# 20190105_ORIGAMI_V1-V.net
KiCad netlist of a schematic drawn in EAGLE
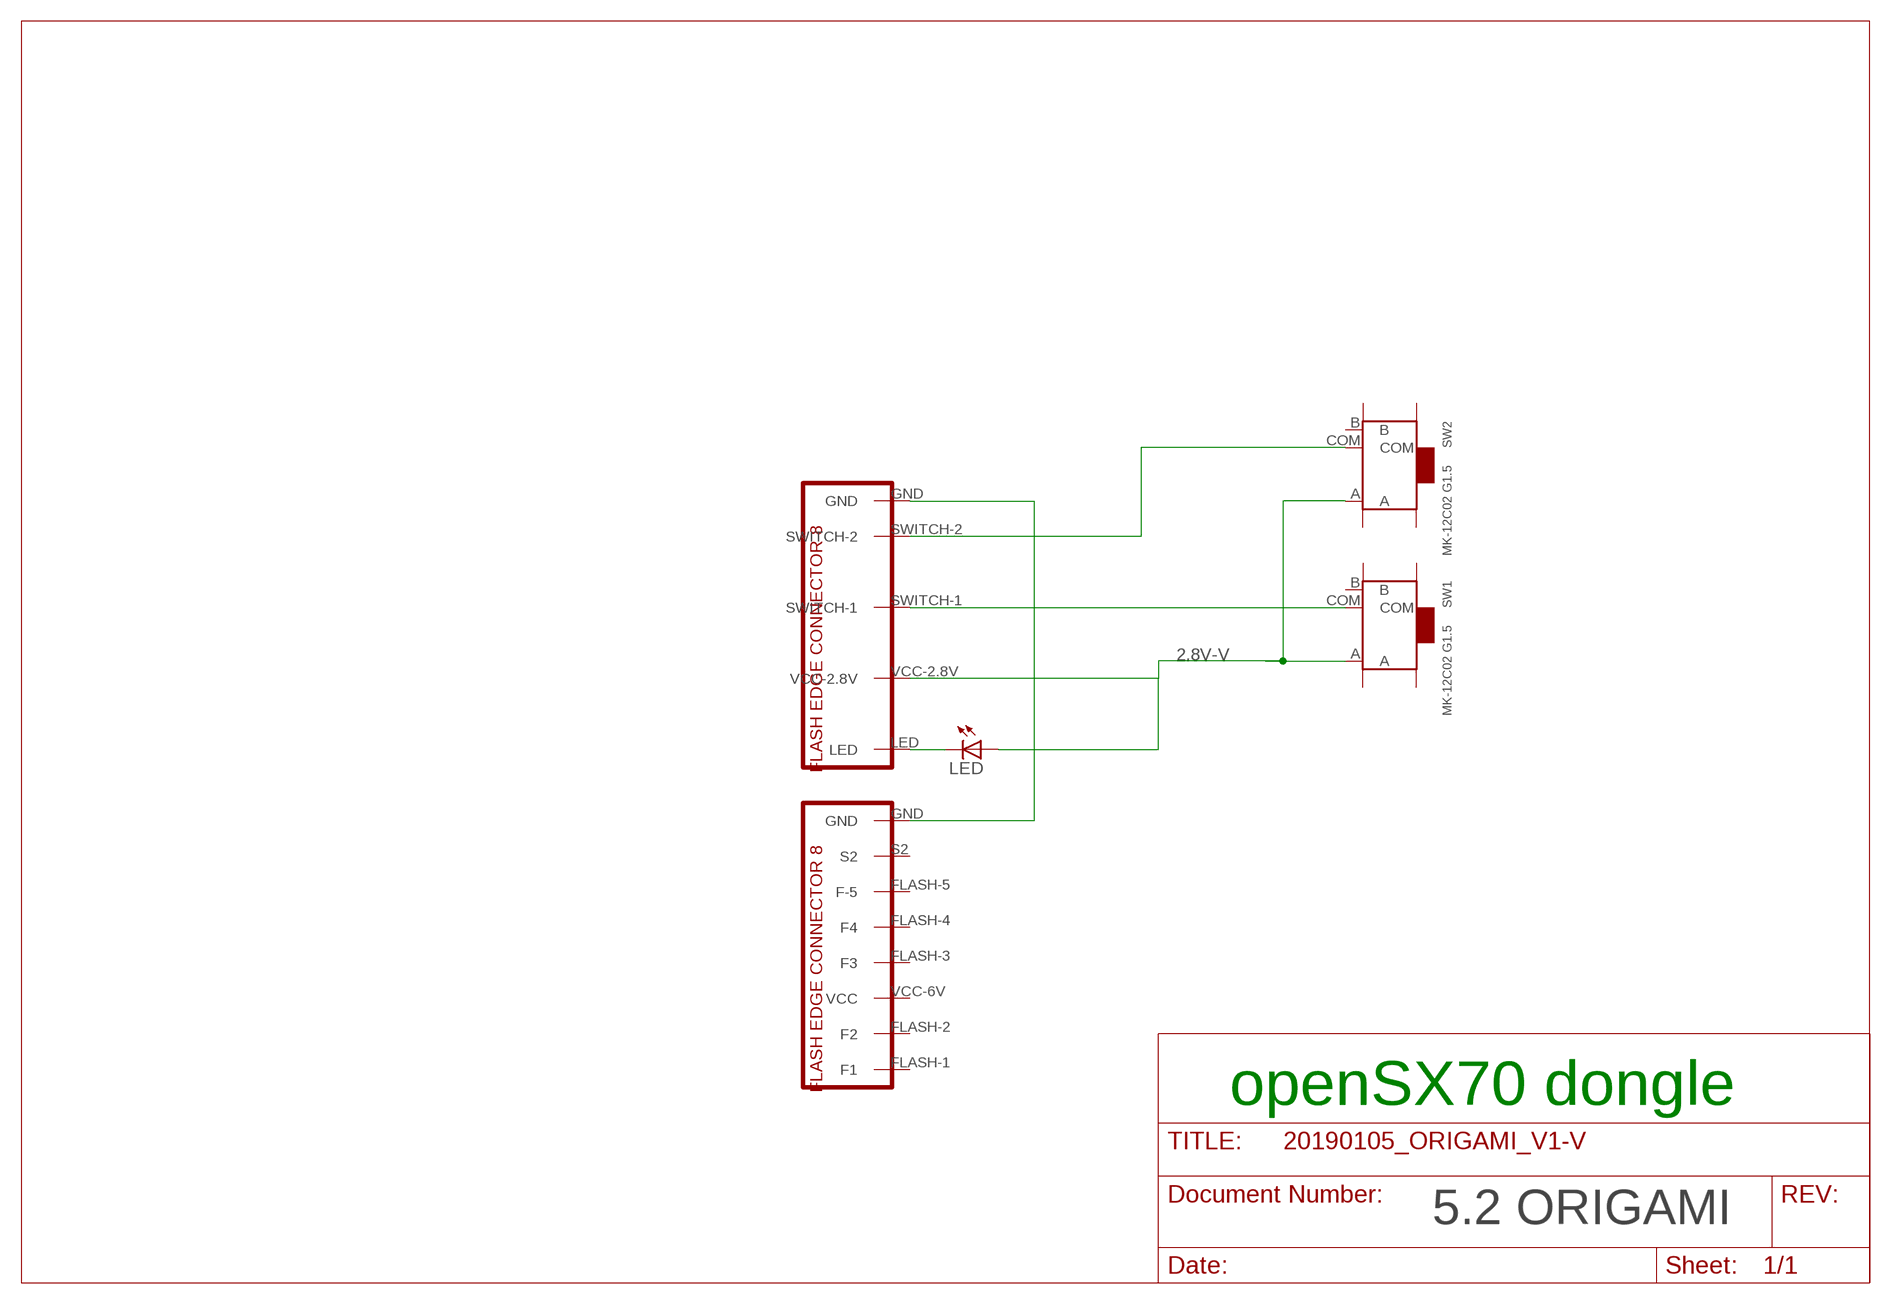
[diagram p0: schematic, sheet 1]

(export (version "E")
  (design (tool "Eeschema 10.0.6"))
  (components
    (comp (ref "LED")
      (value "LEDCHIP-LED0805")
      (footprint "eagle-import:CHIP-LED0805")
      (libsource (lib "eagle-import") (part "LEDCHIP-LED0805"))
    )
    (comp (ref "SW1")
      (value "MK-12C02 G1.5")
      (footprint "eagle-import:SW7-SMD-L6.7X2.7X3.2MM")
      (libsource (lib "eagle-import") (part "SMD-TOGGLE-SWITCH-ON-ON(3+4P-6.7X2.7MM)"))
    )
    (comp (ref "SW2")
      (value "MK-12C02 G1.5")
      (footprint "eagle-import:SW7-SMD-L6.7X2.7X3.2MM")
      (libsource (lib "eagle-import") (part "SMD-TOGGLE-SWITCH-ON-ON(3+4P-6.7X2.7MM)"))
    )
    (comp (ref "U$1")
      (value "FLASH-BRIDGE-SW1-SW2-LED-SMALL")
      (footprint "eagle-import:FLASH-8-BRIDGE-SW1-SW2-LED-SMALL")
      (libsource (lib "eagle-import") (part "FLASH-BRIDGE-SW1-SW2-LED-SMALL"))
    )
    (comp (ref "U$2")
      (value "SX70-FLASH-EDGE8-MALE-LONG")
      (footprint "eagle-import:SX70-FLASH-EDGE8-2")
      (libsource (lib "eagle-import") (part "SX70-FLASH-EDGE8-MALE-LONG"))
    )
  )
  (nets
    (net (code "1") (name "/2.8V-V") (class "Default")
      (node (ref "LED") (pin "A") (pinfunction "A_A") (pintype "passive"))
      (node (ref "SW1") (pin "A") (pinfunction "A_A") (pintype "bidirectional"))
      (node (ref "SW2") (pin "A") (pinfunction "A_A") (pintype "bidirectional"))
      (node (ref "U$1") (pin "VCC-2.8V") (pinfunction "VCC-2.8V_VCC-2.8V") (pintype "bidirectional"))
    )
    (net (code "2") (name "Net-(LED-PadC)") (class "Default")
      (node (ref "LED") (pin "C") (pinfunction "C_C") (pintype "passive"))
      (node (ref "U$1") (pin "LED") (pinfunction "LED_LED") (pintype "bidirectional"))
    )
    (net (code "3") (name "Net-(SW1-PadCOM)") (class "Default")
      (node (ref "SW1") (pin "COM") (pinfunction "COM_COM") (pintype "bidirectional"))
      (node (ref "U$1") (pin "SWITCH-1") (pinfunction "SWITCH-1_SWITCH-1") (pintype "bidirectional"))
    )
    (net (code "4") (name "Net-(SW2-PadCOM)") (class "Default")
      (node (ref "SW2") (pin "COM") (pinfunction "COM_COM") (pintype "bidirectional"))
      (node (ref "U$1") (pin "SWITCH-2") (pinfunction "SWITCH-2_SWITCH-2") (pintype "bidirectional"))
    )
    (net (code "5") (name "Net-(U$1-PadGND)") (class "Default")
      (node (ref "U$1") (pin "GND") (pinfunction "GND_GND") (pintype "bidirectional"))
      (node (ref "U$2") (pin "GND") (pinfunction "GND_GND") (pintype "bidirectional"))
    )
    (net (code "6") (name "unconnected-(SW1-PadB)") (class "Default")
      (node (ref "SW1") (pin "B") (pinfunction "B_B") (pintype "bidirectional"))
    )
    (net (code "7") (name "unconnected-(SW1-PadSS1)") (class "Default")
      (node (ref "SW1") (pin "SS1") (pinfunction "SS1_SS1") (pintype "bidirectional"))
    )
    (net (code "8") (name "unconnected-(SW1-PadSS2)") (class "Default")
      (node (ref "SW1") (pin "SS2") (pinfunction "SS2_SS2") (pintype "bidirectional"))
    )
    (net (code "9") (name "unconnected-(SW1-PadSS3)") (class "Default")
      (node (ref "SW1") (pin "SS3") (pinfunction "SS3_SS3") (pintype "bidirectional"))
    )
    (net (code "10") (name "unconnected-(SW1-PadSS4)") (class "Default")
      (node (ref "SW1") (pin "SS4") (pinfunction "SS4_SS4") (pintype "bidirectional"))
    )
    (net (code "11") (name "unconnected-(SW2-PadB)") (class "Default")
      (node (ref "SW2") (pin "B") (pinfunction "B_B") (pintype "bidirectional"))
    )
    (net (code "12") (name "unconnected-(SW2-PadSS1)") (class "Default")
      (node (ref "SW2") (pin "SS1") (pinfunction "SS1_SS1") (pintype "bidirectional"))
    )
    (net (code "13") (name "unconnected-(SW2-PadSS2)") (class "Default")
      (node (ref "SW2") (pin "SS2") (pinfunction "SS2_SS2") (pintype "bidirectional"))
    )
    (net (code "14") (name "unconnected-(SW2-PadSS3)") (class "Default")
      (node (ref "SW2") (pin "SS3") (pinfunction "SS3_SS3") (pintype "bidirectional"))
    )
    (net (code "15") (name "unconnected-(SW2-PadSS4)") (class "Default")
      (node (ref "SW2") (pin "SS4") (pinfunction "SS4_SS4") (pintype "bidirectional"))
    )
    (net (code "16") (name "unconnected-(U$2-F-5-PadFLASH-5)") (class "Default")
      (node (ref "U$2") (pin "FLASH-5") (pinfunction "F-5_FLASH-5") (pintype "bidirectional"))
    )
    (net (code "17") (name "unconnected-(U$2-F1-PadFLASH-1)") (class "Default")
      (node (ref "U$2") (pin "FLASH-1") (pinfunction "F1_FLASH-1") (pintype "bidirectional"))
    )
    (net (code "18") (name "unconnected-(U$2-F2-PadFLASH-2)") (class "Default")
      (node (ref "U$2") (pin "FLASH-2") (pinfunction "F2_FLASH-2") (pintype "bidirectional"))
    )
    (net (code "19") (name "unconnected-(U$2-F3-PadFLASH-3)") (class "Default")
      (node (ref "U$2") (pin "FLASH-3") (pinfunction "F3_FLASH-3") (pintype "bidirectional"))
    )
    (net (code "20") (name "unconnected-(U$2-F4-PadFLASH-4)") (class "Default")
      (node (ref "U$2") (pin "FLASH-4") (pinfunction "F4_FLASH-4") (pintype "bidirectional"))
    )
    (net (code "21") (name "unconnected-(U$2-PadS2)") (class "Default")
      (node (ref "U$2") (pin "S2") (pinfunction "S2_S2") (pintype "bidirectional"))
    )
    (net (code "22") (name "unconnected-(U$2-VCC-PadVCC-6V)") (class "Default")
      (node (ref "U$2") (pin "VCC-6V") (pinfunction "VCC_VCC-6V") (pintype "bidirectional"))
    )
  )
)
